# joint_board_hall_effect_encoder.net
KiCad netlist of a schematic drawn in Altium Designer
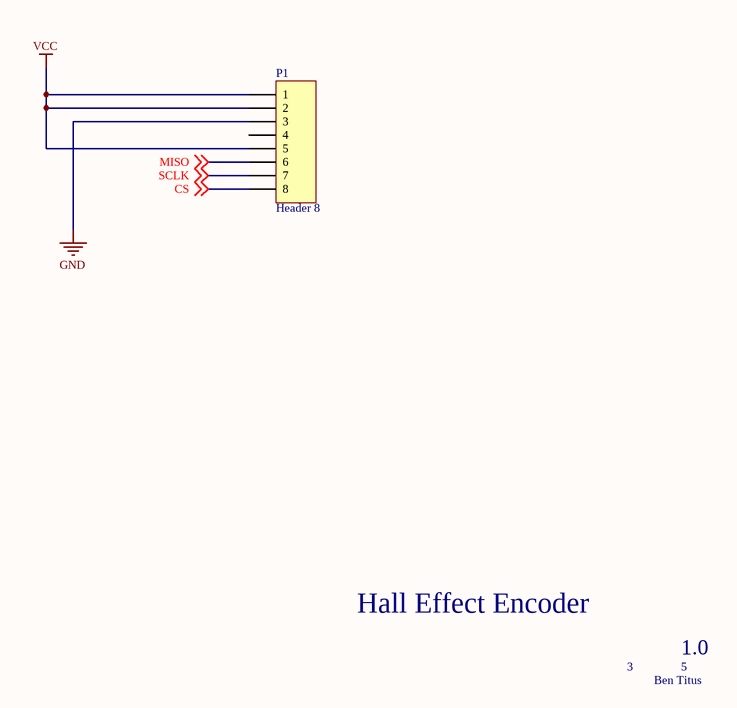
[diagram p0: joint_board_hall_effect_encoder.SchDoc]

(export (version "E")
  (design (tool "Eeschema 10.0.6"))
  (components
    (comp (ref "P1")
      (value "Header 8")
      (footprint "HDR1X8")
      (description "Header, 8-Pin")
      (fields (field (name "PUBLISHER") "Altium Limited"))
      (libsource (lib "Miscellaneous Connectors") (part "Header 8"))
    )
  )
  (nets
    (net (code "1") (name "CS") (class "Default")
      (node (ref "P1") (pin "8") (pinfunction "8_8") (pintype "passive"))
    )
    (net (code "2") (name "GND") (class "Default")
      (node (ref "P1") (pin "3") (pinfunction "3_3") (pintype "passive"))
    )
    (net (code "3") (name "MISO") (class "Default")
      (node (ref "P1") (pin "6") (pinfunction "6_6") (pintype "passive"))
    )
    (net (code "4") (name "SCLK") (class "Default")
      (node (ref "P1") (pin "7") (pinfunction "7_7") (pintype "passive"))
    )
    (net (code "5") (name "VCC") (class "Default")
      (node (ref "P1") (pin "1") (pinfunction "1_1") (pintype "passive"))
      (node (ref "P1") (pin "2") (pinfunction "2_2") (pintype "passive"))
      (node (ref "P1") (pin "5") (pinfunction "5_5") (pintype "passive"))
    )
    (net (code "6") (name "unconnected-(P1-Pad4)") (class "Default")
      (node (ref "P1") (pin "4") (pinfunction "4_4") (pintype "passive"))
    )
  )
)
